# design.net
KiCad netlist of a schematic drawn in EasyEDA Pro
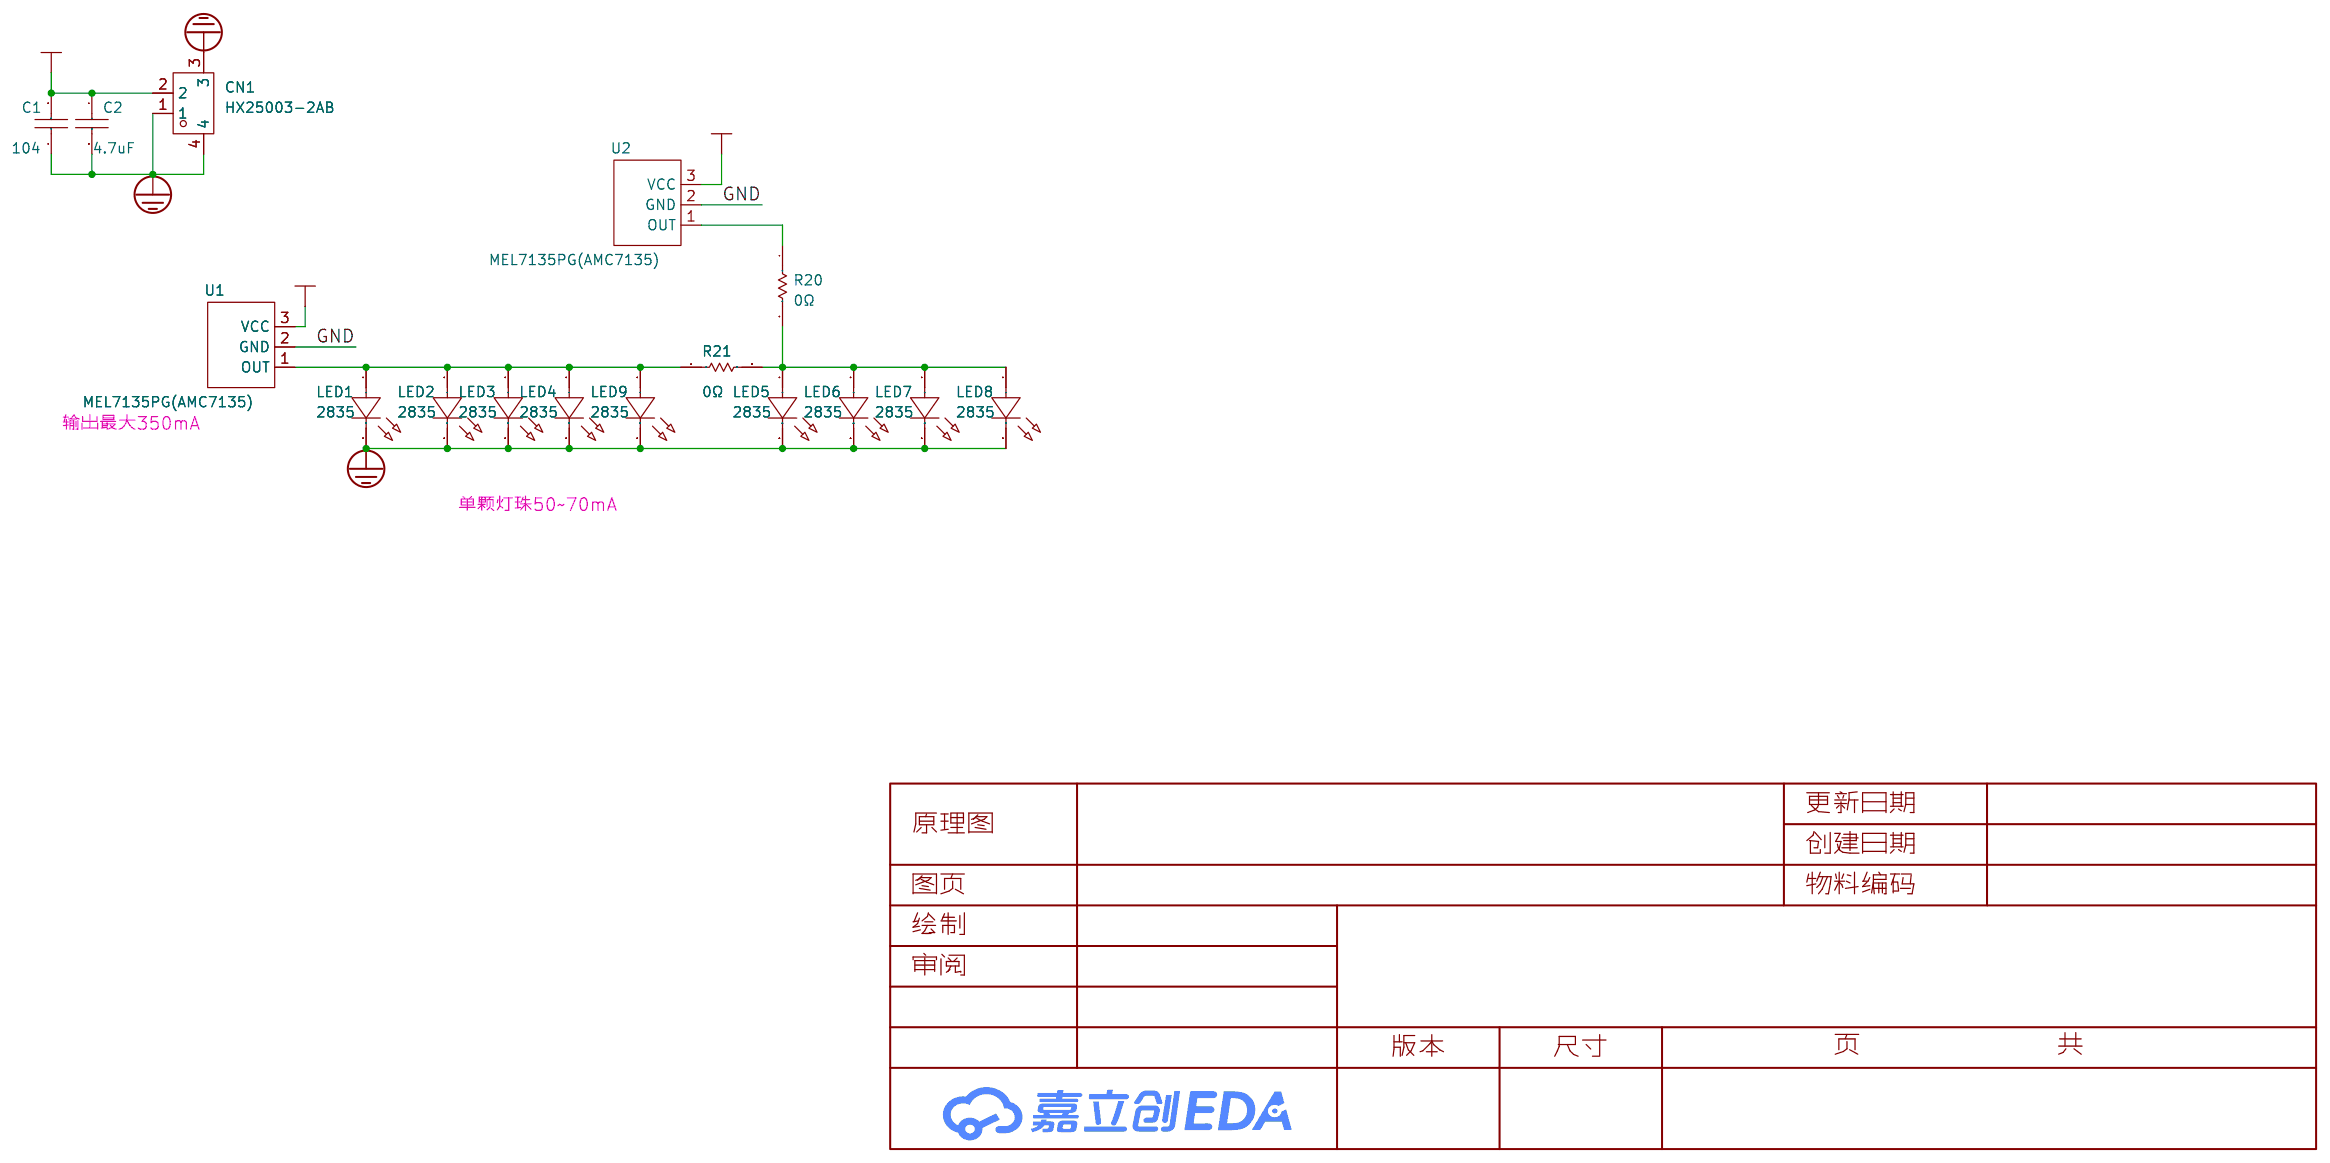
[diagram p0: schematic sheet]

(export (version "E")
  (design (tool "Eeschema 10.0.6"))
  (components
    (comp (ref "C1")
      (value "104")
      (footprint "easyedapro:0603C")
      (description "Capacitor (Semiconductor SIM Model)")
      (libsource (lib "easyedapro") (part "Cap Semi"))
    )
    (comp (ref "C2") (value "4.7uF") (libsource (lib "easyedapro") (part "CAP")))
    (comp (ref "CN1")
      (value "HX25003-2AB")
      (footprint "easyedapro:CONN-SMD_P2.50_HX25003-2AB")
      (fields (field (name "Manufacturer") "HX(红星)"))
      (libsource (lib "easyedapro") (part "HX25003-2AB"))
    )
    (comp (ref "LED1")
      (value "2835")
      (footprint "easyedapro:LED-SMD_L3.5-W2.8_2835")
      (libsource (lib "easyedapro") (part "2835"))
    )
    (comp (ref "LED2")
      (value "2835")
      (footprint "easyedapro:LED-SMD_L3.5-W2.8_2835")
      (libsource (lib "easyedapro") (part "2835"))
    )
    (comp (ref "LED3")
      (value "2835")
      (footprint "easyedapro:LED-SMD_L3.5-W2.8_2835")
      (libsource (lib "easyedapro") (part "2835"))
    )
    (comp (ref "LED4")
      (value "2835")
      (footprint "easyedapro:LED-SMD_L3.5-W2.8_2835")
      (libsource (lib "easyedapro") (part "2835"))
    )
    (comp (ref "LED5")
      (value "2835")
      (footprint "easyedapro:LED-SMD_L3.5-W2.8_2835")
      (libsource (lib "easyedapro") (part "2835"))
    )
    (comp (ref "LED6")
      (value "2835")
      (footprint "easyedapro:LED-SMD_L3.5-W2.8_2835")
      (libsource (lib "easyedapro") (part "2835"))
    )
    (comp (ref "LED7")
      (value "2835")
      (footprint "easyedapro:LED-SMD_L3.5-W2.8_2835")
      (libsource (lib "easyedapro") (part "2835"))
    )
    (comp (ref "LED8")
      (value "2835")
      (footprint "easyedapro:LED-SMD_L3.5-W2.8_2835")
      (libsource (lib "easyedapro") (part "2835"))
    )
    (comp (ref "LED9")
      (value "2835")
      (footprint "easyedapro:LED-SMD_L3.5-W2.8_2835")
      (libsource (lib "easyedapro") (part "2835"))
    )
    (comp (ref "R20")
      (value "0Ω")
      (footprint "easyedapro:10")
      (description "Resistor")
      (libsource (lib "easyedapro") (part "RES"))
    )
    (comp (ref "R21")
      (value "0Ω")
      (footprint "easyedapro:10")
      (description "Resistor")
      (libsource (lib "easyedapro") (part "RES"))
    )
    (comp (ref "U1")
      (value "MEL7135PG(AMC7135)")
      (footprint "easyedapro:SOT-89-3_L4.5-W2.5-P1.50-LS4.2-BR")
      (description "类型:-;工作电压(DC):2.7V~6V;开关频率:-;通道数:1;输出电压:-;输出电流:350mA;调光:-;拓扑结构:-;")
      (fields (field (name "Manufacturer") "MICRONE(南京微盟)"))
      (libsource (lib "easyedapro") (part "MEL7135PG"))
    )
    (comp (ref "U2")
      (value "MEL7135PG(AMC7135)")
      (footprint "easyedapro:SOT-89-3_L4.5-W2.5-P1.50-LS4.2-BR")
      (description "类型:-;工作电压(DC):2.7V~6V;开关频率:-;通道数:1;输出电压:-;输出电流:350mA;调光:-;拓扑结构:-;")
      (fields (field (name "Manufacturer") "MICRONE(南京微盟)"))
      (libsource (lib "easyedapro") (part "MEL7135PG"))
    )
  )
  (nets
    (net (code "1") (name "5V_VCC") (class "Default")
      (node (ref "C1") (pin "2") (pinfunction "2_2") (pintype "unspecified"))
      (node (ref "C2") (pin "1") (pinfunction "1_1") (pintype "input"))
      (node (ref "CN1") (pin "2") (pinfunction "2_2") (pintype "unspecified"))
      (node (ref "U1") (pin "3") (pinfunction "VCC_3") (pintype "unspecified"))
      (node (ref "U2") (pin "3") (pinfunction "VCC_3") (pintype "unspecified"))
    )
    (net (code "2") (name "GND") (class "Default")
      (node (ref "C1") (pin "1") (pinfunction "1_1") (pintype "unspecified"))
      (node (ref "C2") (pin "2") (pinfunction "2_2") (pintype "input"))
      (node (ref "CN1") (pin "1") (pinfunction "1_1") (pintype "unspecified"))
      (node (ref "CN1") (pin "3") (pinfunction "3_3") (pintype "unspecified"))
      (node (ref "CN1") (pin "4") (pinfunction "4_4") (pintype "unspecified"))
      (node (ref "LED1") (pin "2") (pinfunction "C_2") (pintype "unspecified"))
      (node (ref "LED2") (pin "2") (pinfunction "C_2") (pintype "unspecified"))
      (node (ref "LED3") (pin "2") (pinfunction "C_2") (pintype "unspecified"))
      (node (ref "LED4") (pin "2") (pinfunction "C_2") (pintype "unspecified"))
      (node (ref "LED5") (pin "2") (pinfunction "C_2") (pintype "unspecified"))
      (node (ref "LED6") (pin "2") (pinfunction "C_2") (pintype "unspecified"))
      (node (ref "LED7") (pin "2") (pinfunction "C_2") (pintype "unspecified"))
      (node (ref "LED8") (pin "2") (pinfunction "C_2") (pintype "unspecified"))
      (node (ref "LED9") (pin "2") (pinfunction "C_2") (pintype "unspecified"))
      (node (ref "U1") (pin "2") (pinfunction "GND_2") (pintype "unspecified"))
      (node (ref "U2") (pin "2") (pinfunction "GND_2") (pintype "unspecified"))
    )
    (net (code "3") (name "Net-(LED1-A)") (class "Default")
      (node (ref "LED1") (pin "1") (pinfunction "A_1") (pintype "unspecified"))
      (node (ref "LED2") (pin "1") (pinfunction "A_1") (pintype "unspecified"))
      (node (ref "LED3") (pin "1") (pinfunction "A_1") (pintype "unspecified"))
      (node (ref "LED4") (pin "1") (pinfunction "A_1") (pintype "unspecified"))
      (node (ref "LED9") (pin "1") (pinfunction "A_1") (pintype "unspecified"))
      (node (ref "R21") (pin "1") (pinfunction "1_1") (pintype "unspecified"))
      (node (ref "U1") (pin "1") (pinfunction "OUT_1") (pintype "unspecified"))
    )
    (net (code "4") (name "Net-(LED5-A)") (class "Default")
      (node (ref "LED5") (pin "1") (pinfunction "A_1") (pintype "unspecified"))
      (node (ref "LED6") (pin "1") (pinfunction "A_1") (pintype "unspecified"))
      (node (ref "LED7") (pin "1") (pinfunction "A_1") (pintype "unspecified"))
      (node (ref "LED8") (pin "1") (pinfunction "A_1") (pintype "unspecified"))
      (node (ref "R20") (pin "2") (pinfunction "2_2") (pintype "unspecified"))
      (node (ref "R21") (pin "2") (pinfunction "2_2") (pintype "unspecified"))
    )
    (net (code "5") (name "Net-(U2-OUT)") (class "Default")
      (node (ref "R20") (pin "1") (pinfunction "1_1") (pintype "unspecified"))
      (node (ref "U2") (pin "1") (pinfunction "OUT_1") (pintype "unspecified"))
    )
  )
)
